# AMP02.net
KiCad netlist of a schematic drawn in Altium Designer
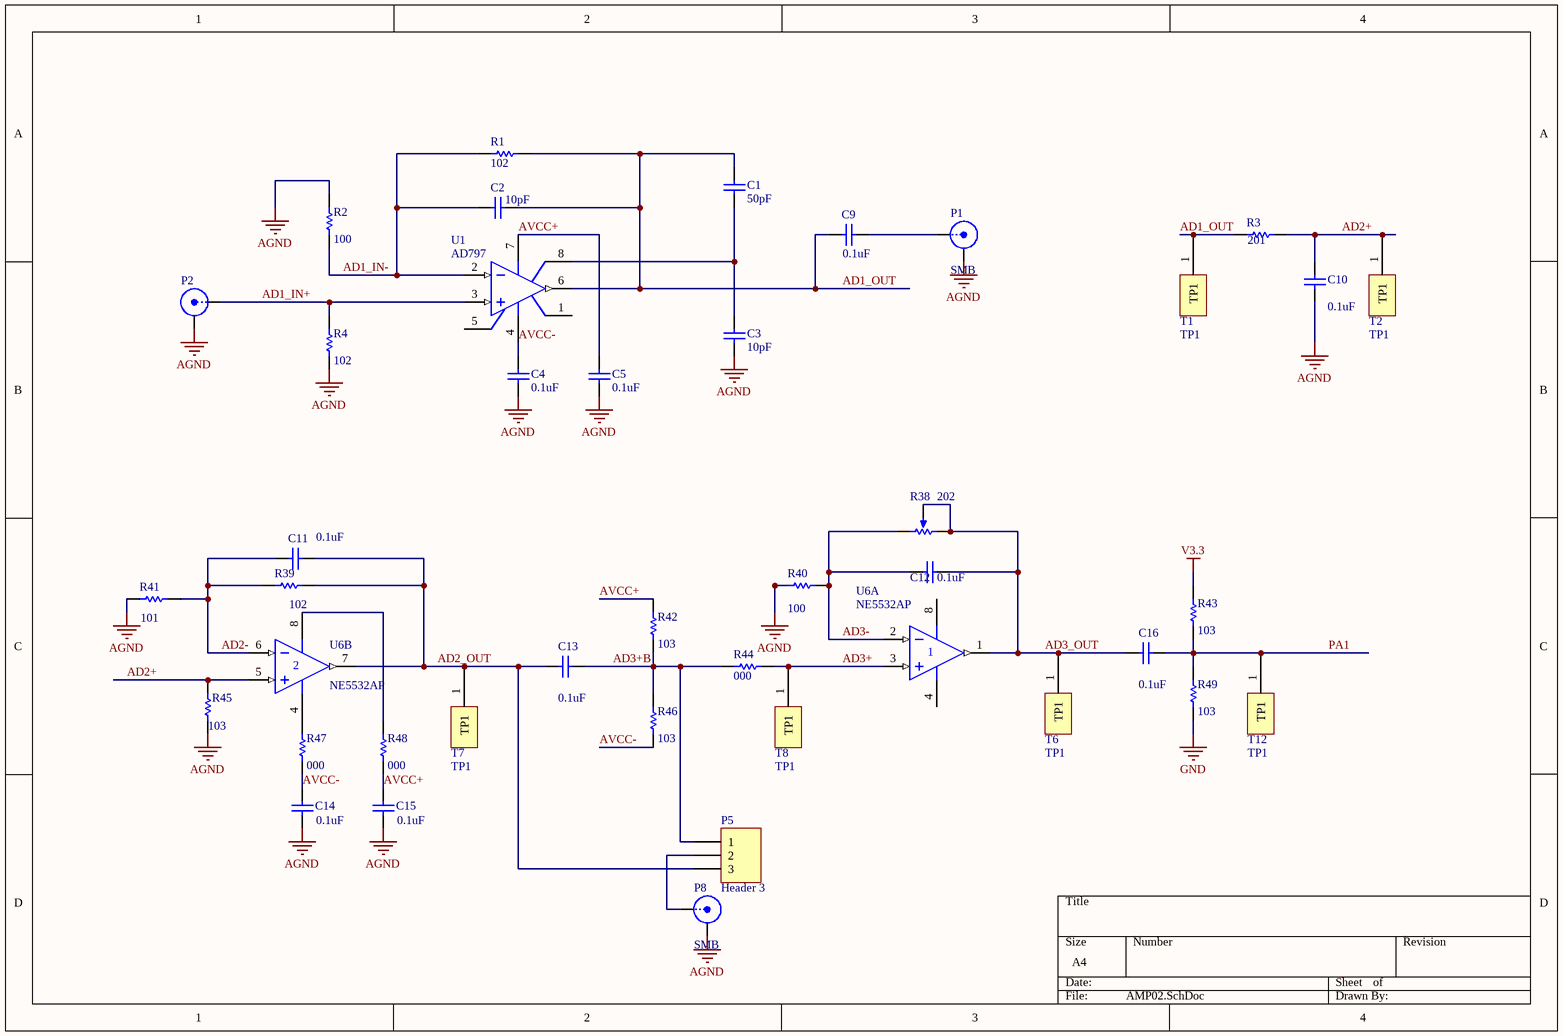
[diagram p0: AMP02.SchDoc]

(export (version "E")
  (design (tool "Eeschema 10.0.6"))
  (components
    (comp (ref "C1")
      (value "50pF")
      (footprint "1206")
      (description "Capacitor (Semiconductor SIM Model)")
      (fields (field (name "Comment") "Cap Semi") (field (name "PUBLISHER") "Altium Limited"))
      (libsource (lib "Miscellaneous Devices") (part "Cap Semi"))
    )
    (comp (ref "C2")
      (value "10pF")
      (footprint "1206")
      (description "Capacitor (Semiconductor SIM Model)")
      (fields (field (name "Comment") "Cap Semi") (field (name "PUBLISHER") "Altium Limited"))
      (libsource (lib "Miscellaneous Devices") (part "Cap Semi"))
    )
    (comp (ref "C3")
      (value "10pF")
      (footprint "1206")
      (description "Capacitor (Semiconductor SIM Model)")
      (fields (field (name "Comment") "Cap Semi") (field (name "PUBLISHER") "Altium Limited"))
      (libsource (lib "Miscellaneous Devices") (part "Cap Semi"))
    )
    (comp (ref "C4")
      (value "0.1uF")
      (footprint "1206")
      (description "Capacitor (Semiconductor SIM Model)")
      (fields (field (name "Comment") "Cap Semi") (field (name "PUBLISHER") "Altium Limited"))
      (libsource (lib "Miscellaneous Devices") (part "Cap Semi"))
    )
    (comp (ref "C5")
      (value "0.1uF")
      (footprint "1206")
      (description "Capacitor (Semiconductor SIM Model)")
      (fields (field (name "Comment") "Cap Semi") (field (name "PUBLISHER") "Altium Limited"))
      (libsource (lib "Miscellaneous Devices") (part "Cap Semi"))
    )
    (comp (ref "C9")
      (value "0.1uF")
      (footprint "1206")
      (description "Capacitor (Semiconductor SIM Model)")
      (fields (field (name "Comment") "Cap Semi") (field (name "PUBLISHER") "Altium Limited"))
      (libsource (lib "Miscellaneous Devices") (part "Cap Semi"))
    )
    (comp (ref "C10")
      (value "0.1uF")
      (footprint "1206")
      (description "Capacitor (Semiconductor SIM Model)")
      (fields (field (name "Comment") "Cap Semi") (field (name "PUBLISHER") "Altium Limited"))
      (libsource (lib "Miscellaneous Devices") (part "Cap Semi"))
    )
    (comp (ref "C11")
      (value "0.1uF")
      (footprint "1206")
      (description "Capacitor (Semiconductor SIM Model)")
      (fields (field (name "Comment") "Cap Semi") (field (name "PUBLISHER") "Altium Limited"))
      (libsource (lib "Miscellaneous Devices") (part "Cap Semi"))
    )
    (comp (ref "C12")
      (value "0.1uF")
      (footprint "1206")
      (description "Capacitor (Semiconductor SIM Model)")
      (fields (field (name "Comment") "Cap Semi") (field (name "PUBLISHER") "Altium Limited"))
      (libsource (lib "Miscellaneous Devices") (part "Cap Semi"))
    )
    (comp (ref "C13")
      (value "0.1uF")
      (footprint "1206")
      (description "Capacitor (Semiconductor SIM Model)")
      (fields (field (name "Comment") "Cap Semi") (field (name "PUBLISHER") "Altium Limited"))
      (libsource (lib "Miscellaneous Devices") (part "Cap Semi"))
    )
    (comp (ref "C14")
      (value "0.1uF")
      (footprint "1206")
      (description "Capacitor (Semiconductor SIM Model)")
      (fields (field (name "Comment") "Cap Semi") (field (name "PUBLISHER") "Altium Limited"))
      (libsource (lib "Miscellaneous Devices") (part "Cap Semi"))
    )
    (comp (ref "C15")
      (value "0.1uF")
      (footprint "1206")
      (description "Capacitor (Semiconductor SIM Model)")
      (fields (field (name "Comment") "Cap Semi") (field (name "PUBLISHER") "Altium Limited"))
      (libsource (lib "Miscellaneous Devices") (part "Cap Semi"))
    )
    (comp (ref "C16")
      (value "0.1uF")
      (footprint "1206")
      (description "Capacitor (Semiconductor SIM Model)")
      (fields (field (name "Comment") "Cap Semi") (field (name "PUBLISHER") "Altium Limited"))
      (libsource (lib "Miscellaneous Devices") (part "Cap Semi"))
    )
    (comp (ref "P1")
      (value "SMB")
      (footprint "SMB_V-RJ45")
      (description "SMB Straight Connector")
      (fields (field (name "PUBLISHER") "Altium Limited"))
      (libsource (lib "Miscellaneous Connectors") (part "SMB"))
    )
    (comp (ref "P2")
      (value "SMB")
      (footprint "SMB_V-RJ45")
      (description "SMB Straight Connector")
      (fields (field (name "PUBLISHER") "Altium Limited"))
      (libsource (lib "Miscellaneous Connectors") (part "SMB"))
    )
    (comp (ref "P5")
      (value "Header 3")
      (footprint "HDR1X3")
      (description "Header, 3-Pin")
      (fields (field (name "PUBLISHER") "Altium Limited"))
      (libsource (lib "Miscellaneous Connectors") (part "Header 3"))
    )
    (comp (ref "P8")
      (value "SMB")
      (footprint "SMB_V-RJ45")
      (description "SMB Straight Connector")
      (fields (field (name "PUBLISHER") "Altium Limited"))
      (libsource (lib "Miscellaneous Connectors") (part "SMB"))
    )
    (comp (ref "R1")
      (value "102")
      (footprint "1206")
      (description "Semiconductor Resistor")
      (fields (field (name "Comment") "Res Semi") (field (name "PUBLISHER") "Altium Limited"))
      (libsource (lib "Miscellaneous Devices") (part "Res Semi"))
    )
    (comp (ref "R2")
      (value "100")
      (footprint "1206")
      (description "Semiconductor Resistor")
      (fields (field (name "Comment") "Res Semi") (field (name "PUBLISHER") "Altium Limited"))
      (libsource (lib "Miscellaneous Devices") (part "Res Semi"))
    )
    (comp (ref "R3")
      (value "201")
      (footprint "1206")
      (description "Semiconductor Resistor")
      (fields (field (name "Comment") "Res Semi") (field (name "PUBLISHER") "Altium Limited"))
      (libsource (lib "Miscellaneous Devices") (part "Res Semi"))
    )
    (comp (ref "R4")
      (value "102")
      (footprint "1206")
      (description "Semiconductor Resistor")
      (fields (field (name "Comment") "Res Semi") (field (name "PUBLISHER") "Altium Limited"))
      (libsource (lib "Miscellaneous Devices") (part "Res Semi"))
    )
    (comp (ref "R38")
      (value "202")
      (footprint "VR5")
      (description "Potentiometer")
      (fields (field (name "Comment") "RPot") (field (name "PUBLISHER") "Altium Limited"))
      (libsource (lib "Miscellaneous Devices") (part "RPot"))
    )
    (comp (ref "R39")
      (value "102")
      (footprint "1206")
      (description "Semiconductor Resistor")
      (fields (field (name "Comment") "Res Semi") (field (name "PUBLISHER") "Altium Limited"))
      (libsource (lib "Miscellaneous Devices") (part "Res Semi"))
    )
    (comp (ref "R40")
      (value "100")
      (footprint "1206")
      (description "Semiconductor Resistor")
      (fields (field (name "Comment") "Res Semi") (field (name "PUBLISHER") "Altium Limited"))
      (libsource (lib "Miscellaneous Devices") (part "Res Semi"))
    )
    (comp (ref "R41")
      (value "101")
      (footprint "1206")
      (description "Semiconductor Resistor")
      (fields (field (name "Comment") "Res Semi") (field (name "PUBLISHER") "Altium Limited"))
      (libsource (lib "Miscellaneous Devices") (part "Res Semi"))
    )
    (comp (ref "R42")
      (value "103")
      (footprint "1206")
      (description "Semiconductor Resistor")
      (fields (field (name "Comment") "Res Semi") (field (name "PUBLISHER") "Altium Limited"))
      (libsource (lib "Miscellaneous Devices") (part "Res Semi"))
    )
    (comp (ref "R43")
      (value "103")
      (description "Semiconductor Resistor")
      (fields (field (name "Comment") "Res Semi") (field (name "PUBLISHER") "Altium Limited"))
      (libsource (lib "Miscellaneous Devices") (part "Res Semi"))
    )
    (comp (ref "R44")
      (value "000")
      (footprint "1206")
      (description "Semiconductor Resistor")
      (fields (field (name "Comment") "Res Semi") (field (name "PUBLISHER") "Altium Limited"))
      (libsource (lib "Miscellaneous Devices") (part "Res Semi"))
    )
    (comp (ref "R45")
      (value "103")
      (footprint "1206")
      (description "Semiconductor Resistor")
      (fields (field (name "Comment") "Res Semi") (field (name "PUBLISHER") "Altium Limited"))
      (libsource (lib "Miscellaneous Devices") (part "Res Semi"))
    )
    (comp (ref "R46")
      (value "103")
      (footprint "1206")
      (description "Semiconductor Resistor")
      (fields (field (name "Comment") "Res Semi") (field (name "PUBLISHER") "Altium Limited"))
      (libsource (lib "Miscellaneous Devices") (part "Res Semi"))
    )
    (comp (ref "R47")
      (value "000")
      (footprint "1206")
      (description "Semiconductor Resistor")
      (fields (field (name "Comment") "Res Semi") (field (name "PUBLISHER") "Altium Limited"))
      (libsource (lib "Miscellaneous Devices") (part "Res Semi"))
    )
    (comp (ref "R48")
      (value "000")
      (footprint "1206")
      (description "Semiconductor Resistor")
      (fields (field (name "Comment") "Res Semi") (field (name "PUBLISHER") "Altium Limited"))
      (libsource (lib "Miscellaneous Devices") (part "Res Semi"))
    )
    (comp (ref "R49")
      (value "103")
      (description "Semiconductor Resistor")
      (fields (field (name "Comment") "Res Semi") (field (name "PUBLISHER") "Altium Limited"))
      (libsource (lib "Miscellaneous Devices") (part "Res Semi"))
    )
    (comp (ref "T1") (value "TP1") (footprint "TP1") (libsource (lib "CHK-I") (part "TP1")))
    (comp (ref "T2") (value "TP1") (footprint "TP1") (libsource (lib "CHK-I") (part "TP1")))
    (comp (ref "T6") (value "TP1") (footprint "TP1") (libsource (lib "CHK-I") (part "TP1")))
    (comp (ref "T7") (value "TP1") (footprint "TP1") (libsource (lib "CHK-I") (part "TP1")))
    (comp (ref "T8") (value "TP1") (footprint "TP1") (libsource (lib "CHK-I") (part "TP1")))
    (comp (ref "T12") (value "TP1") (footprint "TP1") (libsource (lib "CHK-I") (part "TP1")))
    (comp (ref "U1")
      (value "AD797")
      (footprint "SO-8C_M")
      (description "Ultra-Low Distortion, Ultra-Low Noise Operational Amplifier")
      (fields (field (name "PUBLISHER") "Altium Limited"))
      (libsource (lib "AD Operational Amplifier") (part "AD797AR"))
    )
    (comp (ref "U6")
      (value "NE5532AP")
      (footprint "SO-8C_M")
      (description "Dual Low-Noise Operational Amplifier")
      (fields (field (name "PUBLISHER") "Altium Limited"))
      (libsource (lib "TI Operational Amplifier") (part "NE5532AP"))
    )
  )
  (nets
    (net (code "1") (name "/AD1_IN+") (class "Default")
      (node (ref "P2") (pin "1") (pinfunction "X_1") (pintype "passive"))
      (node (ref "R4") (pin "2") (pinfunction "2_2") (pintype "passive"))
      (node (ref "U1") (pin "3") (pinfunction "IN+_3") (pintype "input"))
    )
    (net (code "2") (name "/AD1_IN-") (class "Default")
      (node (ref "C2") (pin "1") (pinfunction "1_1") (pintype "passive"))
      (node (ref "R1") (pin "2") (pinfunction "2_2") (pintype "passive"))
      (node (ref "R2") (pin "1") (pinfunction "1_1") (pintype "passive"))
      (node (ref "U1") (pin "2") (pinfunction "IN-_2") (pintype "input"))
    )
    (net (code "3") (name "/AD1_OUT") (class "Default")
      (node (ref "C1") (pin "2") (pinfunction "2_2") (pintype "passive"))
      (node (ref "C2") (pin "2") (pinfunction "2_2") (pintype "passive"))
      (node (ref "C9") (pin "1") (pinfunction "1_1") (pintype "passive"))
      (node (ref "R1") (pin "1") (pinfunction "1_1") (pintype "passive"))
      (node (ref "R3") (pin "1") (pinfunction "1_1") (pintype "passive"))
      (node (ref "T1") (pin "1") (pinfunction "TP1_1") (pintype "passive"))
      (node (ref "U1") (pin "6") (pinfunction "OUT_6") (pintype "output"))
    )
    (net (code "4") (name "/AD2+") (class "Default")
      (node (ref "C10") (pin "2") (pinfunction "2_2") (pintype "passive"))
      (node (ref "R3") (pin "2") (pinfunction "2_2") (pintype "passive"))
      (node (ref "R45") (pin "2") (pinfunction "2_2") (pintype "passive"))
      (node (ref "T2") (pin "1") (pinfunction "TP1_1") (pintype "passive"))
      (node (ref "U6") (pin "5") (pinfunction "IN+_5") (pintype "input"))
    )
    (net (code "5") (name "/AD2-") (class "Default")
      (node (ref "C11") (pin "1") (pinfunction "1_1") (pintype "passive"))
      (node (ref "R39") (pin "1") (pinfunction "1_1") (pintype "passive"))
      (node (ref "R41") (pin "2") (pinfunction "2_2") (pintype "passive"))
      (node (ref "U6") (pin "6") (pinfunction "IN-_6") (pintype "input"))
    )
    (net (code "6") (name "/AD2_OUT") (class "Default")
      (node (ref "C11") (pin "2") (pinfunction "2_2") (pintype "passive"))
      (node (ref "C13") (pin "1") (pinfunction "1_1") (pintype "passive"))
      (node (ref "P5") (pin "3") (pinfunction "3_3") (pintype "passive"))
      (node (ref "R39") (pin "2") (pinfunction "2_2") (pintype "passive"))
      (node (ref "T7") (pin "1") (pinfunction "TP1_1") (pintype "passive"))
      (node (ref "U6") (pin "7") (pinfunction "OUT_7") (pintype "output"))
    )
    (net (code "7") (name "/AD3+") (class "Default")
      (node (ref "R44") (pin "1") (pinfunction "1_1") (pintype "passive"))
      (node (ref "T8") (pin "1") (pinfunction "TP1_1") (pintype "passive"))
      (node (ref "U6") (pin "3") (pinfunction "IN+_3") (pintype "input"))
    )
    (net (code "8") (name "/AD3+B") (class "Default")
      (node (ref "C13") (pin "2") (pinfunction "2_2") (pintype "passive"))
      (node (ref "P5") (pin "1") (pinfunction "1_1") (pintype "passive"))
      (node (ref "R42") (pin "1") (pinfunction "1_1") (pintype "passive"))
      (node (ref "R44") (pin "2") (pinfunction "2_2") (pintype "passive"))
      (node (ref "R46") (pin "2") (pinfunction "2_2") (pintype "passive"))
    )
    (net (code "9") (name "/AD3-") (class "Default")
      (node (ref "C12") (pin "1") (pinfunction "1_1") (pintype "passive"))
      (node (ref "R38") (pin "2") (pinfunction "BOT_2") (pintype "passive"))
      (node (ref "R40") (pin "2") (pinfunction "2_2") (pintype "passive"))
      (node (ref "U6") (pin "2") (pinfunction "IN-_2") (pintype "input"))
    )
    (net (code "10") (name "/AD3_OUT") (class "Default")
      (node (ref "C12") (pin "2") (pinfunction "2_2") (pintype "passive"))
      (node (ref "C16") (pin "1") (pinfunction "1_1") (pintype "passive"))
      (node (ref "R38") (pin "1") (pinfunction "TOP_1") (pintype "passive"))
      (node (ref "R38") (pin "3") (pinfunction "TAP_3") (pintype "passive"))
      (node (ref "T6") (pin "1") (pinfunction "TP1_1") (pintype "passive"))
      (node (ref "U6") (pin "1") (pinfunction "OUT_1") (pintype "output"))
    )
    (net (code "11") (name "/AVCC+") (class "Default")
      (node (ref "C15") (pin "2") (pinfunction "2_2") (pintype "passive"))
      (node (ref "C5") (pin "2") (pinfunction "2_2") (pintype "passive"))
      (node (ref "R42") (pin "2") (pinfunction "2_2") (pintype "passive"))
      (node (ref "R48") (pin "1") (pinfunction "1_1") (pintype "passive"))
      (node (ref "U1") (pin "7") (pinfunction "V+_7") (pintype "power_in"))
    )
    (net (code "12") (name "/AVCC-") (class "Default")
      (node (ref "C14") (pin "2") (pinfunction "2_2") (pintype "passive"))
      (node (ref "C4") (pin "2") (pinfunction "2_2") (pintype "passive"))
      (node (ref "R46") (pin "1") (pinfunction "1_1") (pintype "passive"))
      (node (ref "R47") (pin "1") (pinfunction "1_1") (pintype "passive"))
      (node (ref "U1") (pin "4") (pinfunction "V-_4") (pintype "power_in"))
    )
    (net (code "13") (name "/PA1") (class "Default")
      (node (ref "C16") (pin "2") (pinfunction "2_2") (pintype "passive"))
      (node (ref "R43") (pin "1") (pinfunction "1_1") (pintype "passive"))
      (node (ref "R49") (pin "2") (pinfunction "2_2") (pintype "passive"))
      (node (ref "T12") (pin "1") (pinfunction "TP1_1") (pintype "passive"))
    )
    (net (code "14") (name "AGND") (class "Default")
      (node (ref "C10") (pin "1") (pinfunction "1_1") (pintype "passive"))
      (node (ref "C14") (pin "1") (pinfunction "1_1") (pintype "passive"))
      (node (ref "C15") (pin "1") (pinfunction "1_1") (pintype "passive"))
      (node (ref "C3") (pin "1") (pinfunction "1_1") (pintype "passive"))
      (node (ref "C4") (pin "1") (pinfunction "1_1") (pintype "passive"))
      (node (ref "C5") (pin "1") (pinfunction "1_1") (pintype "passive"))
      (node (ref "P1") (pin "2") (pinfunction "Y_2") (pintype "passive"))
      (node (ref "P2") (pin "2") (pinfunction "Y_2") (pintype "passive"))
      (node (ref "P8") (pin "2") (pinfunction "Y_2") (pintype "passive"))
      (node (ref "R2") (pin "2") (pinfunction "2_2") (pintype "passive"))
      (node (ref "R4") (pin "1") (pinfunction "1_1") (pintype "passive"))
      (node (ref "R40") (pin "1") (pinfunction "1_1") (pintype "passive"))
      (node (ref "R41") (pin "1") (pinfunction "1_1") (pintype "passive"))
      (node (ref "R45") (pin "1") (pinfunction "1_1") (pintype "passive"))
    )
    (net (code "15") (name "GND") (class "Default")
      (node (ref "R49") (pin "1") (pinfunction "1_1") (pintype "passive"))
    )
    (net (code "16") (name "Net-(P1-X)") (class "Default")
      (node (ref "C9") (pin "2") (pinfunction "2_2") (pintype "passive"))
      (node (ref "P1") (pin "1") (pinfunction "X_1") (pintype "passive"))
    )
    (net (code "17") (name "Net-(P8-X)") (class "Default")
      (node (ref "P5") (pin "2") (pinfunction "2_2") (pintype "passive"))
      (node (ref "P8") (pin "1") (pinfunction "X_1") (pintype "passive"))
    )
    (net (code "18") (name "Net-(U1-DECMPEN)") (class "Default")
      (node (ref "C1") (pin "1") (pinfunction "1_1") (pintype "passive"))
      (node (ref "C3") (pin "2") (pinfunction "2_2") (pintype "passive"))
      (node (ref "U1") (pin "8") (pinfunction "DECMPEN_8") (pintype "passive"))
    )
    (net (code "19") (name "Net-(U6B-V+)") (class "Default")
      (node (ref "R48") (pin "2") (pinfunction "2_2") (pintype "passive"))
      (node (ref "U6") (pin "8") (pinfunction "V+_8") (pintype "power_in"))
    )
    (net (code "20") (name "Net-(U6B-V-)") (class "Default")
      (node (ref "R47") (pin "2") (pinfunction "2_2") (pintype "passive"))
      (node (ref "U6") (pin "4") (pinfunction "V-_4") (pintype "power_in"))
    )
    (net (code "21") (name "V3.3") (class "Default")
      (node (ref "R43") (pin "2") (pinfunction "2_2") (pintype "passive"))
    )
    (net (code "22") (name "unconnected-(U1-OS_NUL-Pad1)") (class "Default")
      (node (ref "U1") (pin "1") (pinfunction "OS_NUL_1") (pintype "passive"))
    )
    (net (code "23") (name "unconnected-(U1-OS_NUL-Pad5)") (class "Default")
      (node (ref "U1") (pin "5") (pinfunction "OS_NUL_5") (pintype "passive"))
    )
    (net (code "24") (name "unconnected-(U6A-V+-Pad8)") (class "Default")
      (node (ref "U6") (pin "8") (pinfunction "V+_8") (pintype "power_in"))
    )
    (net (code "25") (name "unconnected-(U6A-V--Pad4)") (class "Default")
      (node (ref "U6") (pin "4") (pinfunction "V-_4") (pintype "power_in"))
    )
  )
)
